# SDRAM.net
KiCad netlist of a schematic drawn in Altium Designer
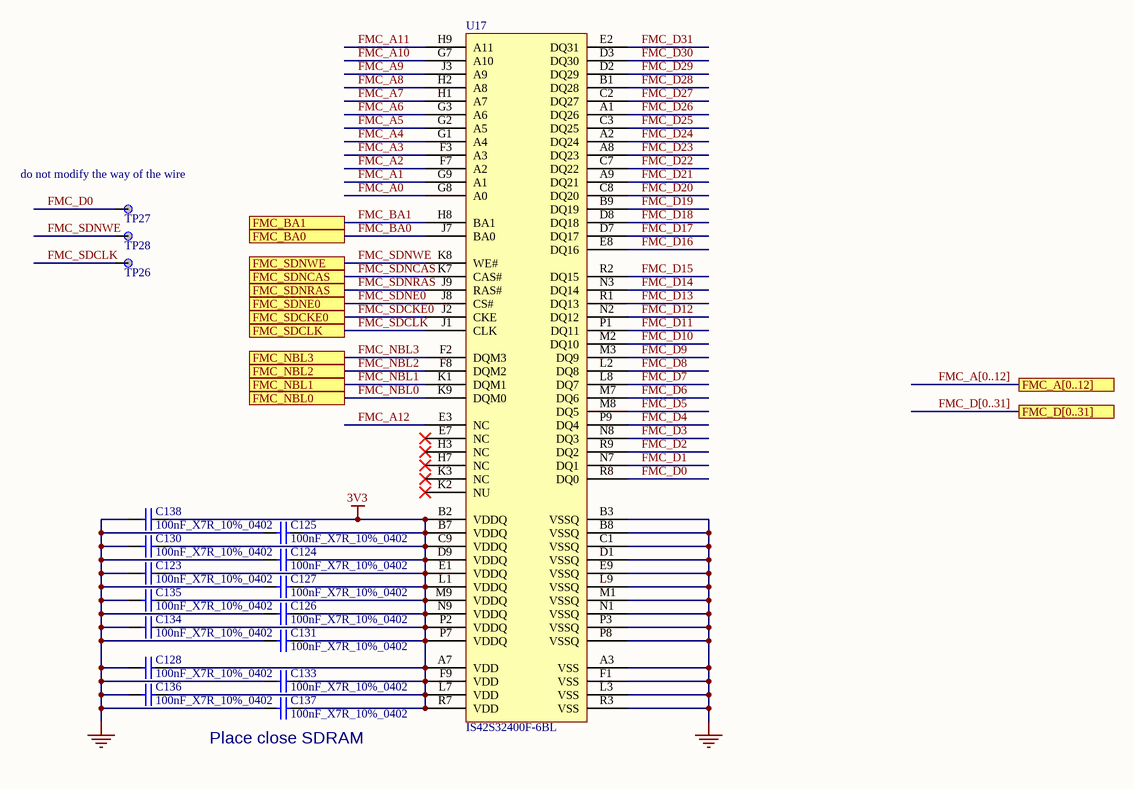
[diagram p0: SDRAM.SchDoc]

(export (version "E")
  (design (tool "Eeschema 10.0.6"))
  (components
    (comp (ref "C123")
      (value "100nF_X7R_10%_0402")
      (footprint "0402C")
      (description "Capacitor,100nF,16V,X7R,10%,0402,YAGEO")
      (libsource (lib "MCD_TOOLS") (part "Cap_100nF_X7R_10%_0402"))
    )
    (comp (ref "C124")
      (value "100nF_X7R_10%_0402")
      (footprint "0402C")
      (description "Capacitor,100nF,16V,X7R,10%,0402,YAGEO")
      (libsource (lib "MCD_TOOLS") (part "Cap_100nF_X7R_10%_0402"))
    )
    (comp (ref "C125")
      (value "100nF_X7R_10%_0402")
      (footprint "0402C")
      (description "Capacitor,100nF,16V,X7R,10%,0402,YAGEO")
      (libsource (lib "MCD_TOOLS") (part "Cap_100nF_X7R_10%_0402"))
    )
    (comp (ref "C126")
      (value "100nF_X7R_10%_0402")
      (footprint "0402C")
      (description "Capacitor,100nF,16V,X7R,10%,0402,YAGEO")
      (libsource (lib "MCD_TOOLS") (part "Cap_100nF_X7R_10%_0402"))
    )
    (comp (ref "C127")
      (value "100nF_X7R_10%_0402")
      (footprint "0402C")
      (description "Capacitor,100nF,16V,X7R,10%,0402,YAGEO")
      (libsource (lib "MCD_TOOLS") (part "Cap_100nF_X7R_10%_0402"))
    )
    (comp (ref "C128")
      (value "100nF_X7R_10%_0402")
      (footprint "0402C")
      (description "Capacitor,100nF,16V,X7R,10%,0402,YAGEO")
      (libsource (lib "MCD_TOOLS") (part "Cap_100nF_X7R_10%_0402"))
    )
    (comp (ref "C130")
      (value "100nF_X7R_10%_0402")
      (footprint "0402C")
      (description "Capacitor,100nF,16V,X7R,10%,0402,YAGEO")
      (libsource (lib "MCD_TOOLS") (part "Cap_100nF_X7R_10%_0402"))
    )
    (comp (ref "C131")
      (value "100nF_X7R_10%_0402")
      (footprint "0402C")
      (description "Capacitor,100nF,16V,X7R,10%,0402,YAGEO")
      (libsource (lib "MCD_TOOLS") (part "Cap_100nF_X7R_10%_0402"))
    )
    (comp (ref "C133")
      (value "100nF_X7R_10%_0402")
      (footprint "0402C")
      (description "Capacitor,100nF,16V,X7R,10%,0402,YAGEO")
      (libsource (lib "MCD_TOOLS") (part "Cap_100nF_X7R_10%_0402"))
    )
    (comp (ref "C134")
      (value "100nF_X7R_10%_0402")
      (footprint "0402C")
      (description "Capacitor,100nF,16V,X7R,10%,0402,YAGEO")
      (libsource (lib "MCD_TOOLS") (part "Cap_100nF_X7R_10%_0402"))
    )
    (comp (ref "C135")
      (value "100nF_X7R_10%_0402")
      (footprint "0402C")
      (description "Capacitor,100nF,16V,X7R,10%,0402,YAGEO")
      (libsource (lib "MCD_TOOLS") (part "Cap_100nF_X7R_10%_0402"))
    )
    (comp (ref "C136")
      (value "100nF_X7R_10%_0402")
      (footprint "0402C")
      (description "Capacitor,100nF,16V,X7R,10%,0402,YAGEO")
      (libsource (lib "MCD_TOOLS") (part "Cap_100nF_X7R_10%_0402"))
    )
    (comp (ref "C137")
      (value "100nF_X7R_10%_0402")
      (footprint "0402C")
      (description "Capacitor,100nF,16V,X7R,10%,0402,YAGEO")
      (libsource (lib "MCD_TOOLS") (part "Cap_100nF_X7R_10%_0402"))
    )
    (comp (ref "C138")
      (value "100nF_X7R_10%_0402")
      (footprint "0402C")
      (description "Capacitor,100nF,16V,X7R,10%,0402,YAGEO")
      (libsource (lib "MCD_TOOLS") (part "Cap_100nF_X7R_10%_0402"))
    )
    (comp (ref "TP26")
      (value "TP")
      (footprint "TP_C40")
      (description "Test Point")
      (libsource (lib "MCD_TOOLS_CONNECTOR") (part "TP"))
    )
    (comp (ref "TP27")
      (value "TP")
      (footprint "TP_C40")
      (description "Test Point")
      (libsource (lib "MCD_TOOLS_CONNECTOR") (part "TP"))
    )
    (comp (ref "TP28")
      (value "TP")
      (footprint "TP_C40")
      (description "Test Point")
      (libsource (lib "MCD_TOOLS_CONNECTOR") (part "TP"))
    )
    (comp (ref "U17")
      (value "IS42S32400F-6BL")
      (footprint "ICC_VFBGA90_8X13_P080")
      (description "SDRAM 128MBit 166MHZ 90BGA")
      (fields (field (name "INTERNAL_PART_NUMBER") "MCD-01977") (field (name "MANUFACTURER") "ISSI"))
      (libsource (lib "MCD_PARTS_database") (part "IS42S32400F-6BL"))
    )
  )
  (nets
    (net (code "1") (name "/FMC_A0") (class "Default")
      (node (ref "U17") (pin "G8") (pinfunction "A0_G8") (pintype "passive"))
    )
    (net (code "2") (name "/FMC_A1") (class "Default")
      (node (ref "U17") (pin "G9") (pinfunction "A1_G9") (pintype "passive"))
    )
    (net (code "3") (name "/FMC_A2") (class "Default")
      (node (ref "U17") (pin "F7") (pinfunction "A2_F7") (pintype "passive"))
    )
    (net (code "4") (name "/FMC_A3") (class "Default")
      (node (ref "U17") (pin "F3") (pinfunction "A3_F3") (pintype "passive"))
    )
    (net (code "5") (name "/FMC_A4") (class "Default")
      (node (ref "U17") (pin "G1") (pinfunction "A4_G1") (pintype "passive"))
    )
    (net (code "6") (name "/FMC_A5") (class "Default")
      (node (ref "U17") (pin "G2") (pinfunction "A5_G2") (pintype "passive"))
    )
    (net (code "7") (name "/FMC_A6") (class "Default")
      (node (ref "U17") (pin "G3") (pinfunction "A6_G3") (pintype "passive"))
    )
    (net (code "8") (name "/FMC_A7") (class "Default")
      (node (ref "U17") (pin "H1") (pinfunction "A7_H1") (pintype "passive"))
    )
    (net (code "9") (name "/FMC_A8") (class "Default")
      (node (ref "U17") (pin "H2") (pinfunction "A8_H2") (pintype "passive"))
    )
    (net (code "10") (name "/FMC_A9") (class "Default")
      (node (ref "U17") (pin "J3") (pinfunction "A9_J3") (pintype "passive"))
    )
    (net (code "11") (name "/FMC_A10") (class "Default")
      (node (ref "U17") (pin "G7") (pinfunction "A10_G7") (pintype "passive"))
    )
    (net (code "12") (name "/FMC_A11") (class "Default")
      (node (ref "U17") (pin "H9") (pinfunction "A11_H9") (pintype "passive"))
    )
    (net (code "13") (name "/FMC_A12") (class "Default")
      (node (ref "U17") (pin "E3") (pinfunction "NC_E3") (pintype "passive"))
    )
    (net (code "15") (name "/FMC_BA0") (class "Default")
      (node (ref "U17") (pin "J7") (pinfunction "BA0_J7") (pintype "passive"))
    )
    (net (code "16") (name "/FMC_BA1") (class "Default")
      (node (ref "U17") (pin "H8") (pinfunction "BA1_H8") (pintype "passive"))
    )
    (net (code "17") (name "/FMC_D0") (class "Default")
      (node (ref "TP27") (pin "1") (pinfunction "1_1") (pintype "passive"))
      (node (ref "U17") (pin "R8") (pinfunction "DQ0_R8") (pintype "passive"))
    )
    (net (code "18") (name "/FMC_D1") (class "Default")
      (node (ref "U17") (pin "N7") (pinfunction "DQ1_N7") (pintype "passive"))
    )
    (net (code "19") (name "/FMC_D2") (class "Default")
      (node (ref "U17") (pin "R9") (pinfunction "DQ2_R9") (pintype "passive"))
    )
    (net (code "20") (name "/FMC_D3") (class "Default")
      (node (ref "U17") (pin "N8") (pinfunction "DQ3_N8") (pintype "passive"))
    )
    (net (code "21") (name "/FMC_D4") (class "Default")
      (node (ref "U17") (pin "P9") (pinfunction "DQ4_P9") (pintype "passive"))
    )
    (net (code "22") (name "/FMC_D5") (class "Default")
      (node (ref "U17") (pin "M8") (pinfunction "DQ5_M8") (pintype "passive"))
    )
    (net (code "23") (name "/FMC_D6") (class "Default")
      (node (ref "U17") (pin "M7") (pinfunction "DQ6_M7") (pintype "passive"))
    )
    (net (code "24") (name "/FMC_D7") (class "Default")
      (node (ref "U17") (pin "L8") (pinfunction "DQ7_L8") (pintype "passive"))
    )
    (net (code "25") (name "/FMC_D8") (class "Default")
      (node (ref "U17") (pin "L2") (pinfunction "DQ8_L2") (pintype "passive"))
    )
    (net (code "26") (name "/FMC_D9") (class "Default")
      (node (ref "U17") (pin "M3") (pinfunction "DQ9_M3") (pintype "passive"))
    )
    (net (code "27") (name "/FMC_D10") (class "Default")
      (node (ref "U17") (pin "M2") (pinfunction "DQ10_M2") (pintype "passive"))
    )
    (net (code "28") (name "/FMC_D11") (class "Default")
      (node (ref "U17") (pin "P1") (pinfunction "DQ11_P1") (pintype "passive"))
    )
    (net (code "29") (name "/FMC_D12") (class "Default")
      (node (ref "U17") (pin "N2") (pinfunction "DQ12_N2") (pintype "passive"))
    )
    (net (code "30") (name "/FMC_D13") (class "Default")
      (node (ref "U17") (pin "R1") (pinfunction "DQ13_R1") (pintype "passive"))
    )
    (net (code "31") (name "/FMC_D14") (class "Default")
      (node (ref "U17") (pin "N3") (pinfunction "DQ14_N3") (pintype "passive"))
    )
    (net (code "32") (name "/FMC_D15") (class "Default")
      (node (ref "U17") (pin "R2") (pinfunction "DQ15_R2") (pintype "passive"))
    )
    (net (code "33") (name "/FMC_D16") (class "Default")
      (node (ref "U17") (pin "E8") (pinfunction "DQ16_E8") (pintype "passive"))
    )
    (net (code "34") (name "/FMC_D17") (class "Default")
      (node (ref "U17") (pin "D7") (pinfunction "DQ17_D7") (pintype "passive"))
    )
    (net (code "35") (name "/FMC_D18") (class "Default")
      (node (ref "U17") (pin "D8") (pinfunction "DQ18_D8") (pintype "passive"))
    )
    (net (code "36") (name "/FMC_D19") (class "Default")
      (node (ref "U17") (pin "B9") (pinfunction "DQ19_B9") (pintype "passive"))
    )
    (net (code "37") (name "/FMC_D20") (class "Default")
      (node (ref "U17") (pin "C8") (pinfunction "DQ20_C8") (pintype "passive"))
    )
    (net (code "38") (name "/FMC_D21") (class "Default")
      (node (ref "U17") (pin "A9") (pinfunction "DQ21_A9") (pintype "passive"))
    )
    (net (code "39") (name "/FMC_D22") (class "Default")
      (node (ref "U17") (pin "C7") (pinfunction "DQ22_C7") (pintype "passive"))
    )
    (net (code "40") (name "/FMC_D23") (class "Default")
      (node (ref "U17") (pin "A8") (pinfunction "DQ23_A8") (pintype "passive"))
    )
    (net (code "41") (name "/FMC_D24") (class "Default")
      (node (ref "U17") (pin "A2") (pinfunction "DQ24_A2") (pintype "passive"))
    )
    (net (code "42") (name "/FMC_D25") (class "Default")
      (node (ref "U17") (pin "C3") (pinfunction "DQ25_C3") (pintype "passive"))
    )
    (net (code "43") (name "/FMC_D26") (class "Default")
      (node (ref "U17") (pin "A1") (pinfunction "DQ26_A1") (pintype "passive"))
    )
    (net (code "44") (name "/FMC_D27") (class "Default")
      (node (ref "U17") (pin "C2") (pinfunction "DQ27_C2") (pintype "passive"))
    )
    (net (code "45") (name "/FMC_D28") (class "Default")
      (node (ref "U17") (pin "B1") (pinfunction "DQ28_B1") (pintype "passive"))
    )
    (net (code "46") (name "/FMC_D29") (class "Default")
      (node (ref "U17") (pin "D2") (pinfunction "DQ29_D2") (pintype "passive"))
    )
    (net (code "47") (name "/FMC_D30") (class "Default")
      (node (ref "U17") (pin "D3") (pinfunction "DQ30_D3") (pintype "passive"))
    )
    (net (code "48") (name "/FMC_D31") (class "Default")
      (node (ref "U17") (pin "E2") (pinfunction "DQ31_E2") (pintype "passive"))
    )
    (net (code "50") (name "/FMC_NBL0") (class "Default")
      (node (ref "U17") (pin "K9") (pinfunction "DQM0_K9") (pintype "passive"))
    )
    (net (code "51") (name "/FMC_NBL1") (class "Default")
      (node (ref "U17") (pin "K1") (pinfunction "DQM1_K1") (pintype "passive"))
    )
    (net (code "52") (name "/FMC_NBL2") (class "Default")
      (node (ref "U17") (pin "F8") (pinfunction "DQM2_F8") (pintype "passive"))
    )
    (net (code "53") (name "/FMC_NBL3") (class "Default")
      (node (ref "U17") (pin "F2") (pinfunction "DQM3_F2") (pintype "passive"))
    )
    (net (code "54") (name "/FMC_SDCKE0") (class "Default")
      (node (ref "U17") (pin "J2") (pinfunction "CKE_J2") (pintype "passive"))
    )
    (net (code "55") (name "/FMC_SDCLK") (class "Default")
      (node (ref "TP26") (pin "1") (pinfunction "1_1") (pintype "passive"))
      (node (ref "U17") (pin "J1") (pinfunction "CLK_J1") (pintype "passive"))
    )
    (net (code "56") (name "/FMC_SDNCAS") (class "Default")
      (node (ref "U17") (pin "K7") (pinfunction "CAS#_K7") (pintype "passive"))
    )
    (net (code "57") (name "/FMC_SDNE0") (class "Default")
      (node (ref "U17") (pin "J8") (pinfunction "CS#_J8") (pintype "passive"))
    )
    (net (code "58") (name "/FMC_SDNRAS") (class "Default")
      (node (ref "U17") (pin "J9") (pinfunction "RAS#_J9") (pintype "passive"))
    )
    (net (code "59") (name "/FMC_SDNWE") (class "Default")
      (node (ref "TP28") (pin "1") (pinfunction "1_1") (pintype "passive"))
      (node (ref "U17") (pin "K8") (pinfunction "WE#_K8") (pintype "passive"))
    )
    (net (code "60") (name "3V3") (class "Default")
      (node (ref "C123") (pin "2") (pinfunction "2_2") (pintype "passive"))
      (node (ref "C124") (pin "2") (pinfunction "2_2") (pintype "passive"))
      (node (ref "C125") (pin "2") (pinfunction "2_2") (pintype "passive"))
      (node (ref "C126") (pin "2") (pinfunction "2_2") (pintype "passive"))
      (node (ref "C127") (pin "2") (pinfunction "2_2") (pintype "passive"))
      (node (ref "C128") (pin "2") (pinfunction "2_2") (pintype "passive"))
      (node (ref "C130") (pin "2") (pinfunction "2_2") (pintype "passive"))
      (node (ref "C131") (pin "2") (pinfunction "2_2") (pintype "passive"))
      (node (ref "C133") (pin "2") (pinfunction "2_2") (pintype "passive"))
      (node (ref "C134") (pin "2") (pinfunction "2_2") (pintype "passive"))
      (node (ref "C135") (pin "2") (pinfunction "2_2") (pintype "passive"))
      (node (ref "C136") (pin "2") (pinfunction "2_2") (pintype "passive"))
      (node (ref "C137") (pin "2") (pinfunction "2_2") (pintype "passive"))
      (node (ref "C138") (pin "2") (pinfunction "2_2") (pintype "passive"))
      (node (ref "U17") (pin "A7") (pinfunction "VDD_A7") (pintype "passive"))
      (node (ref "U17") (pin "B2") (pinfunction "VDDQ_B2") (pintype "passive"))
      (node (ref "U17") (pin "B7") (pinfunction "VDDQ_B7") (pintype "passive"))
      (node (ref "U17") (pin "C9") (pinfunction "VDDQ_C9") (pintype "passive"))
      (node (ref "U17") (pin "D9") (pinfunction "VDDQ_D9") (pintype "passive"))
      (node (ref "U17") (pin "E1") (pinfunction "VDDQ_E1") (pintype "passive"))
      (node (ref "U17") (pin "F9") (pinfunction "VDD_F9") (pintype "passive"))
      (node (ref "U17") (pin "L1") (pinfunction "VDDQ_L1") (pintype "passive"))
      (node (ref "U17") (pin "L7") (pinfunction "VDD_L7") (pintype "passive"))
      (node (ref "U17") (pin "M9") (pinfunction "VDDQ_M9") (pintype "passive"))
      (node (ref "U17") (pin "N9") (pinfunction "VDDQ_N9") (pintype "passive"))
      (node (ref "U17") (pin "P2") (pinfunction "VDDQ_P2") (pintype "passive"))
      (node (ref "U17") (pin "P7") (pinfunction "VDDQ_P7") (pintype "passive"))
      (node (ref "U17") (pin "R7") (pinfunction "VDD_R7") (pintype "passive"))
    )
    (net (code "61") (name "GND") (class "Default")
      (node (ref "C123") (pin "1") (pinfunction "1_1") (pintype "passive"))
      (node (ref "C124") (pin "1") (pinfunction "1_1") (pintype "passive"))
      (node (ref "C125") (pin "1") (pinfunction "1_1") (pintype "passive"))
      (node (ref "C126") (pin "1") (pinfunction "1_1") (pintype "passive"))
      (node (ref "C127") (pin "1") (pinfunction "1_1") (pintype "passive"))
      (node (ref "C128") (pin "1") (pinfunction "1_1") (pintype "passive"))
      (node (ref "C130") (pin "1") (pinfunction "1_1") (pintype "passive"))
      (node (ref "C131") (pin "1") (pinfunction "1_1") (pintype "passive"))
      (node (ref "C133") (pin "1") (pinfunction "1_1") (pintype "passive"))
      (node (ref "C134") (pin "1") (pinfunction "1_1") (pintype "passive"))
      (node (ref "C135") (pin "1") (pinfunction "1_1") (pintype "passive"))
      (node (ref "C136") (pin "1") (pinfunction "1_1") (pintype "passive"))
      (node (ref "C137") (pin "1") (pinfunction "1_1") (pintype "passive"))
      (node (ref "C138") (pin "1") (pinfunction "1_1") (pintype "passive"))
      (node (ref "U17") (pin "A3") (pinfunction "VSS_A3") (pintype "passive"))
      (node (ref "U17") (pin "B3") (pinfunction "VSSQ_B3") (pintype "passive"))
      (node (ref "U17") (pin "B8") (pinfunction "VSSQ_B8") (pintype "passive"))
      (node (ref "U17") (pin "C1") (pinfunction "VSSQ_C1") (pintype "passive"))
      (node (ref "U17") (pin "D1") (pinfunction "VSSQ_D1") (pintype "passive"))
      (node (ref "U17") (pin "E9") (pinfunction "VSSQ_E9") (pintype "passive"))
      (node (ref "U17") (pin "F1") (pinfunction "VSS_F1") (pintype "passive"))
      (node (ref "U17") (pin "L3") (pinfunction "VSS_L3") (pintype "passive"))
      (node (ref "U17") (pin "L9") (pinfunction "VSSQ_L9") (pintype "passive"))
      (node (ref "U17") (pin "M1") (pinfunction "VSSQ_M1") (pintype "passive"))
      (node (ref "U17") (pin "N1") (pinfunction "VSSQ_N1") (pintype "passive"))
      (node (ref "U17") (pin "P3") (pinfunction "VSSQ_P3") (pintype "passive"))
      (node (ref "U17") (pin "P8") (pinfunction "VSSQ_P8") (pintype "passive"))
      (node (ref "U17") (pin "R3") (pinfunction "VSS_R3") (pintype "passive"))
    )
    (net (code "62") (name "unconnected-(U17-NC-PadE7)") (class "Default")
      (node (ref "U17") (pin "E7") (pinfunction "NC_E7") (pintype "passive+no_connect"))
    )
    (net (code "63") (name "unconnected-(U17-NC-PadH3)") (class "Default")
      (node (ref "U17") (pin "H3") (pinfunction "NC_H3") (pintype "passive+no_connect"))
    )
    (net (code "64") (name "unconnected-(U17-NC-PadH7)") (class "Default")
      (node (ref "U17") (pin "H7") (pinfunction "NC_H7") (pintype "passive+no_connect"))
    )
    (net (code "65") (name "unconnected-(U17-NC-PadK3)") (class "Default")
      (node (ref "U17") (pin "K3") (pinfunction "NC_K3") (pintype "passive+no_connect"))
    )
    (net (code "66") (name "unconnected-(U17-NU-PadK2)") (class "Default")
      (node (ref "U17") (pin "K2") (pinfunction "NU_K2") (pintype "passive+no_connect"))
    )
  )
)
